# Sheet1.net
KiCad netlist of a schematic drawn in Altium Designer
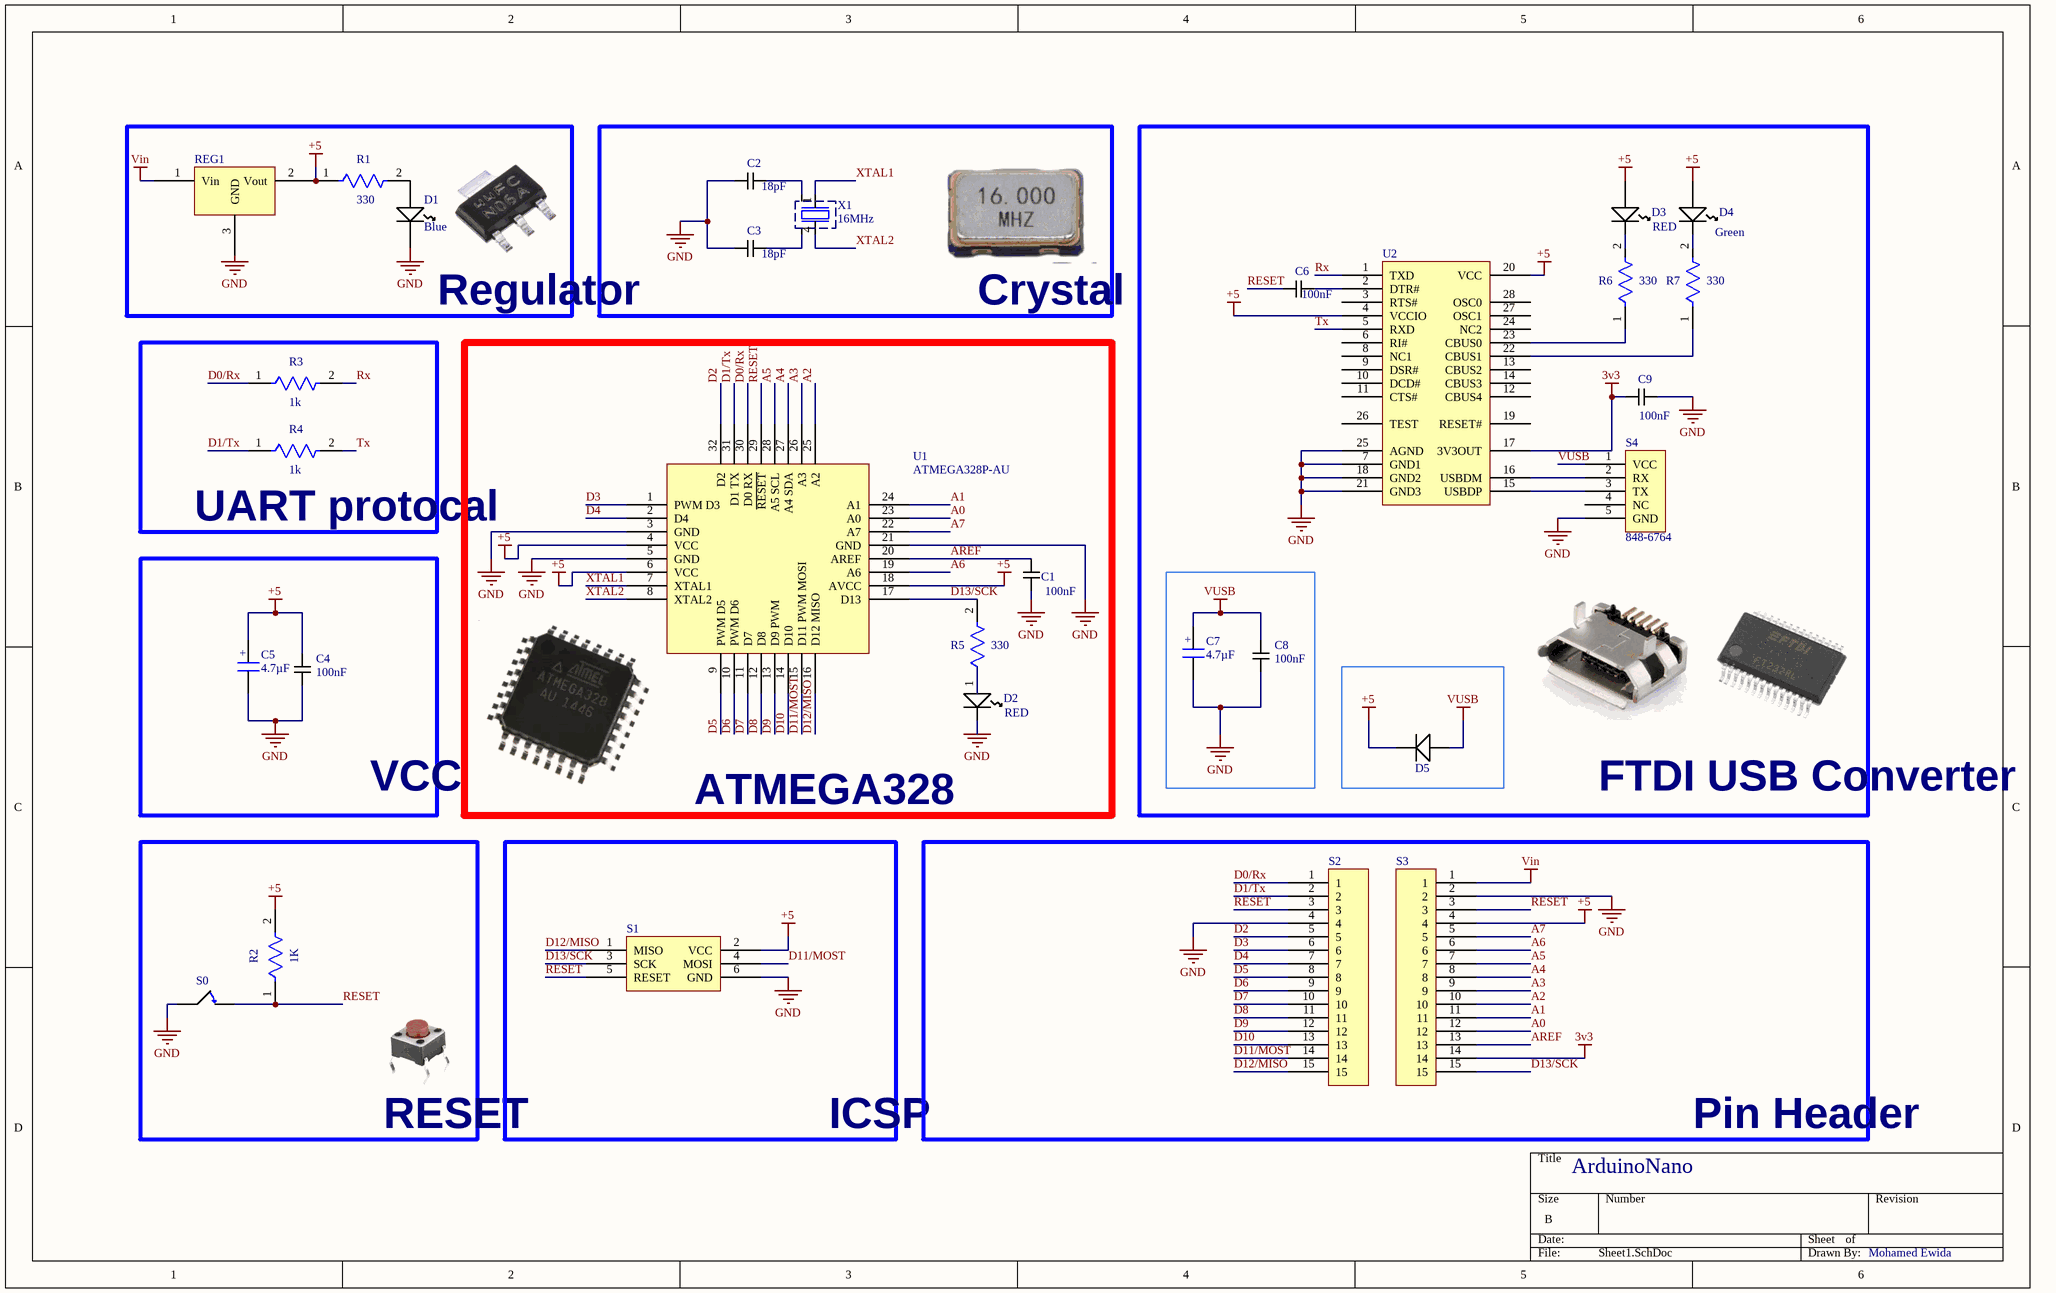
[diagram p0: Sheet1.SchDoc]

(export (version "E")
  (design (tool "Eeschema 10.0.6"))
  (components
    (comp (ref "C1")
      (value "100nF Ceramic Multilayer Capacitor_1")
      (footprint "CAPCP2012X09N")
      (description "AVX 0805 Standard 100nF Ceramic Multilayer Capacitor, 50 V dc X7R Dielectric ±10% SMD")
      (fields
        (field (name "MANUFACTURER") "AVX")
        (field (name "VOLTAGE") "50V")
        (field (name "CAPACITANCE") "100nF")
        (field (name "CREATOR") "Ritesh Kanjee")
      )
      (libsource (lib "RS Components - Capacitors") (part "100nF Ceramic Multilayer Capacitor_1"))
    )
    (comp (ref "C2")
      (value "C0805C180J5GACTU")
      (footprint "CAPCP2012X09N")
      (description "18pF Ceramic Multilayer Capacitor, 50 V dc C0G Dielectric ±5% SMD")
      (fields
        (field (name "MANUFACTURER") "Kemet")
        (field (name "VOLTAGE") "50V")
        (field (name "CAPACITANCE") "18pF")
        (field (name "CREATOR") "Ritesh Kanjee")
      )
      (libsource (lib "RS Components - Capacitors") (part "18pF Ceramic Multilayer Capacitor, 50 V dc C0G Dielectric ±5% SMD"))
    )
    (comp (ref "C3")
      (value "C0805C180J5GACTU")
      (footprint "CAPCP2012X09N")
      (description "18pF Ceramic Multilayer Capacitor, 50 V dc C0G Dielectric ±5% SMD")
      (fields
        (field (name "MANUFACTURER") "Kemet")
        (field (name "VOLTAGE") "50V")
        (field (name "CAPACITANCE") "18pF")
        (field (name "CREATOR") "Ritesh Kanjee")
      )
      (libsource (lib "RS Components - Capacitors") (part "18pF Ceramic Multilayer Capacitor, 50 V dc C0G Dielectric ±5% SMD"))
    )
    (comp (ref "C4")
      (value "100nF Ceramic Multilayer Capacitor_1")
      (footprint "CAPCP2012X09N")
      (description "AVX 0805 Standard 100nF Ceramic Multilayer Capacitor, 50 V dc X7R Dielectric ±10% SMD")
      (fields
        (field (name "MANUFACTURER") "AVX")
        (field (name "VOLTAGE") "50V")
        (field (name "CAPACITANCE") "100nF")
        (field (name "CREATOR") "Ritesh Kanjee")
      )
      (libsource (lib "RS Components - Capacitors") (part "100nF Ceramic Multilayer Capacitor_1"))
    )
    (comp (ref "C5")
      (value "4.7µF")
      (footprint "CASE A - 3216X18")
      (description "Capacitor,tantalum,SMT,16V,4.7uF,10%,A-case")
      (fields
        (field (name "TOLERANCE") "10%")
        (field (name "VOLTAGE") "16V")
        (field (name "PUBLISHER") "DPSS")
      )
      (libsource (lib "RS Components - Capacitors") (part "4.7µF Tant RS 496-3545"))
    )
    (comp (ref "C6")
      (value "100nF Ceramic Multilayer Capacitor_1")
      (footprint "CAPCP2012X09N")
      (description "AVX 0805 Standard 100nF Ceramic Multilayer Capacitor, 50 V dc X7R Dielectric ±10% SMD")
      (fields
        (field (name "MANUFACTURER") "AVX")
        (field (name "VOLTAGE") "50V")
        (field (name "CAPACITANCE") "100nF")
        (field (name "CREATOR") "Ritesh Kanjee")
      )
      (libsource (lib "RS Components - Capacitors") (part "100nF Ceramic Multilayer Capacitor_1"))
    )
    (comp (ref "C7")
      (value "4.7µF")
      (footprint "CASE A - 3216X18")
      (description "Capacitor,tantalum,SMT,16V,4.7uF,10%,A-case")
      (fields
        (field (name "TOLERANCE") "10%")
        (field (name "VOLTAGE") "16V")
        (field (name "PUBLISHER") "DPSS")
      )
      (libsource (lib "RS Components - Capacitors") (part "4.7µF Tant RS 496-3545"))
    )
    (comp (ref "C8")
      (value "100nF Ceramic Multilayer Capacitor_1")
      (footprint "CAPCP2012X09N")
      (description "AVX 0805 Standard 100nF Ceramic Multilayer Capacitor, 50 V dc X7R Dielectric ±10% SMD")
      (fields
        (field (name "MANUFACTURER") "AVX")
        (field (name "VOLTAGE") "50V")
        (field (name "CAPACITANCE") "100nF")
        (field (name "CREATOR") "Ritesh Kanjee")
      )
      (libsource (lib "RS Components - Capacitors") (part "100nF Ceramic Multilayer Capacitor_1"))
    )
    (comp (ref "C9")
      (value "100nF Ceramic Multilayer Capacitor_1")
      (footprint "CAPCP2012X09N")
      (description "AVX 0805 Standard 100nF Ceramic Multilayer Capacitor, 50 V dc X7R Dielectric ±10% SMD")
      (fields
        (field (name "MANUFACTURER") "AVX")
        (field (name "VOLTAGE") "50V")
        (field (name "CAPACITANCE") "100nF")
        (field (name "CREATOR") "Ritesh Kanjee")
      )
      (libsource (lib "RS Components - Capacitors") (part "100nF Ceramic Multilayer Capacitor_1"))
    )
    (comp (ref "D1")
      (value "Kingbright Blue LED, 60 mcd 120 ° 0805")
      (footprint "LED1913X12NBLUE")
      (fields
        (field (name "MANUFACTURER") "KingBright")
        (field (name "MANUFACTURER PART NO.") "KP-2012PBC-A")
        (field (name "CREATOR") "Ritesh Kanjee")
      )
      (libsource (lib "KingBright LEDs") (part "Kingbright Blue LED, 60 mcd 120 ° 0805"))
    )
    (comp (ref "D2")
      (value "Kingbright Red LED, 100 mcd 120 ° 0805")
      (footprint "LED1913X12NRED")
      (fields
        (field (name "MANUFACTURER") "KingBright")
        (field (name "MANUFACTURER PART NO.") "KP-2012SRC-PRV")
        (field (name "COLOR") "RED")
        (field (name "CREATOR") "Ritesh Kanjee")
      )
      (libsource (lib "KingBright LEDs") (part "Kingbright Red LED, 100 mcd 120 ° 0805"))
    )
    (comp (ref "D3")
      (value "Kingbright Red LED, 100 mcd 120 ° 0805")
      (footprint "LED1913X12NRED")
      (fields
        (field (name "MANUFACTURER") "KingBright")
        (field (name "MANUFACTURER PART NO.") "KP-2012SRC-PRV")
        (field (name "COLOR") "RED")
        (field (name "CREATOR") "Ritesh Kanjee")
      )
      (libsource (lib "KingBright LEDs") (part "Kingbright Red LED, 100 mcd 120 ° 0805"))
    )
    (comp (ref "D4")
      (value "Kingbright Green LED, 70 mcd 120 ° 0805")
      (footprint "LED1913X12NGREEN")
      (fields
        (field (name "MANUFACTURER") "KingBright")
        (field (name "MANUFACTURER PART NO.") "KP-2012MGC")
        (field (name "COLOR") "Green")
        (field (name "CREATOR") "Ritesh Kanjee")
      )
      (libsource (lib "KingBright LEDs") (part "Kingbright Green LED, 70 mcd 120 ° 0805"))
    )
    (comp (ref "D5")
      (value "Panasonic DB2J20900L Schottky Diode, 0.5A, 20V, 2.4ns, 2-Pin SMini2 F5 B")
      (footprint "DIOM1712X07N")
      (fields
        (field (name "MANUFACTURER") "Panasonic")
        (field (name "MANUFACTURER PART NO.") "DB2J20900L")
        (field (name "CREATED BY") "R Kanjee")
      )
      (libsource (lib "Panasonic Diodes") (part "Schottky Diode, 0.5A, 20V, 2.4ns, 2-Pin SMini2 F5 B"))
    )
    (comp (ref "R1")
      (value "ERA-3AEB102V")
      (footprint "FP-ERA3A-IPC_C")
      (description "RES SMD 1K OHM 0.1% 1/10W 0603")
      (fields (field (name "TOLERANCE") "0.1%"))
      (libsource (lib "Altium Content Vault") (part "1029c3af85768c4190bb7ad29bc67b5"))
    )
    (comp (ref "R2")
      (value "ERA-3AEB102V")
      (footprint "FP-ERA3A-IPC_C")
      (description "RES SMD 1K OHM 0.1% 1/10W 0603")
      (fields (field (name "TOLERANCE") "0.1%"))
      (libsource (lib "Altium Content Vault") (part "1029c3af85768c4190bb7ad29bc67b5"))
    )
    (comp (ref "R3")
      (value "ERA-3AEB102V")
      (footprint "FP-ERA3A-IPC_C")
      (description "RES SMD 1K OHM 0.1% 1/10W 0603")
      (fields (field (name "TOLERANCE") "0.1%") (field (name "RESISTANCE") "1k"))
      (libsource (lib "Altium Content Vault") (part "1029c3af85768c4190bb7ad29bc67b5"))
    )
    (comp (ref "R4")
      (value "ERA-3AEB102V")
      (footprint "FP-ERA3A-IPC_C")
      (description "RES SMD 1K OHM 0.1% 1/10W 0603")
      (fields (field (name "TOLERANCE") "0.1%") (field (name "RESISTANCE") "1k"))
      (libsource (lib "Altium Content Vault") (part "1029c3af85768c4190bb7ad29bc67b5"))
    )
    (comp (ref "R5")
      (value "ERA-3AEB102V")
      (footprint "FP-ERA3A-IPC_C")
      (description "RES SMD 1K OHM 0.1% 1/10W 0603")
      (fields (field (name "TOLERANCE") "0.1%") (field (name "RESISTANCE") "330"))
      (libsource (lib "Altium Content Vault") (part "1029c3af85768c4190bb7ad29bc67b5"))
    )
    (comp (ref "R6")
      (value "ERA-3AEB102V")
      (footprint "FP-ERA3A-IPC_C")
      (description "RES SMD 1K OHM 0.1% 1/10W 0603")
      (fields (field (name "TOLERANCE") "0.1%") (field (name "RESISTANCE") "330"))
      (libsource (lib "Altium Content Vault") (part "1029c3af85768c4190bb7ad29bc67b5"))
    )
    (comp (ref "R7")
      (value "ERA-3AEB102V")
      (footprint "FP-ERA3A-IPC_C")
      (description "RES SMD 1K OHM 0.1% 1/10W 0603")
      (fields (field (name "TOLERANCE") "0.1%") (field (name "RESISTANCE") "330"))
      (libsource (lib "Altium Content Vault") (part "1029c3af85768c4190bb7ad29bc67b5"))
    )
    (comp (ref "REG1")
      (value "LM1117MP-5.0/NOPB, Low Dropout Voltage Regulator, 1.5A, 5 V ±1%, 4-Pin SOT-223")
      (footprint "SOT230P700X180-4N")
      (fields (field (name "MANUFACTURER") "Texas Instruments") (field (name "CREATED BY") "R Kanjee"))
      (libsource (lib "TI Low Dropout Voltage Regulator") (part "LM1117MP-5.0"))
    )
    (comp (ref "S0")
      (value "Tactile Switch SPST- NO 0.05A @24V")
      (footprint "Tactile Switch")
      (fields
        (field (name "MANUFACTURER") "Omron")
        (field (name "MANUFACTURER PART NO.") "B3F1000")
        (field (name "CREATOR") "R Kanjee")
      )
      (libsource (lib "Omron Tactile Switches") (part "Tactile Switch SPST- NO 0.05A @24V"))
    )
    (comp (ref "S1")
      (value "Programming Headers Dual Row")
      (footprint "ISP HEADER")
      (fields
        (field (name "MANUFACTURER") "FCI")
        (field (name "MANUFACTURER PART NO.") "68000-236HLF")
        (field (name "CREATED BY") "R Kanjee")
      )
      (libsource (lib "PCB Headers") (part "Programming ISP, Programming Headers Dual Row"))
    )
    (comp (ref "S2")
      (value "connector;str header;single row;.1 cont centers;.095 tail;gold or gtx;36 contact")
      (footprint "Header")
      (fields
        (field (name "MANUFACTURER") "FCI")
        (field (name "MANUFACTURER PART NO.") "68000-236HLF")
        (field (name "CREATED BY") "R Kanjee")
      )
      (libsource (lib "PCB Headers") (part "Single row; PCB headers"))
    )
    (comp (ref "S3")
      (value "connector;str header;single row;.1 cont centers;.095 tail;gold or gtx;36 contact")
      (footprint "Header")
      (fields
        (field (name "MANUFACTURER") "FCI")
        (field (name "MANUFACTURER PART NO.") "68000-236HLF")
        (field (name "CREATED BY") "R Kanjee")
      )
      (libsource (lib "") (part "Single row; PCB headers_1"))
    )
    (comp (ref "S4")
      (value "NewMolex Right Angle SMT Female Type B Micro USB Connector, 30 V ac, 1.8A")
      (footprint "MicroUSB")
      (fields
        (field (name "MANUFACTURER") "Molex")
        (field (name "MANUFACTURER PART NO.") "105017-0001")
        (field (name "RS STOCK NO") "848-6764")
        (field (name "CREATOR") "R Kanjee")
      )
      (libsource (lib "Molex Connectors") (part "Micro USB Connector, 30 V ac, 1.8A"))
    )
    (comp (ref "U1")
      (value "ATMEGA328P-AU")
      (footprint "TQFP80P900X900X120-32N")
      (description "ATMEGA328P-AU, 8 bit AVR Microcontroller 20MHz 1 kB, 32 kB Flash, 2 kB RAM, I2C 32-Pin TQFP")
      (fields (field (name "CREATED BY") "Ritesh Kanjee"))
      (libsource (lib "Atmel Microcontrollers") (part "ATMEGA328P-AU"))
    )
    (comp (ref "U2")
      (value "FT232RL, Universal Asynchronous Receiver & Transmitter 3MBd, 28-Pin, SSOP")
      (footprint "SOP65P780X200-28N")
      (fields
        (field (name "MANUFACTURER PART NO.") "FT232RL")
        (field (name "MANUFACTURER") "FTDI Chip")
        (field (name "CREATOR") "R Kanjee")
      )
      (libsource (lib "FTDI RS232toUSB") (part "FT232RL USB to UART, Universal Asynchronous Receiver & Transmitter 3MBd, 28-Pin, SSOP"))
    )
    (comp (ref "X1")
      (value "16MHz")
      (footprint "Aker S5C Crystal")
      (description "Aker S5C SMT Crystal")
      (fields
        (field (name "MANUFACTURER") "Aker")
        (field (name "MANUFACTURER PART #") "C5S-16.000-12-3030-X")
        (field (name "CREATOR") "R Kanjee")
      )
      (libsource (lib "Aker Crystals") (part "Aker  C5S-16.000-12-3030-X"))
    )
  )
  (nets
    (net (code "1") (name "+5") (class "Default")
      (node (ref "C4") (pin "2") (pinfunction "2_2") (pintype "passive"))
      (node (ref "C5") (pin "1") (pinfunction "1_1") (pintype "passive"))
      (node (ref "D3") (pin "1") (pinfunction "A_1") (pintype "passive"))
      (node (ref "D4") (pin "1") (pinfunction "A_1") (pintype "passive"))
      (node (ref "D5") (pin "1") (pinfunction "1_1") (pintype "passive"))
      (node (ref "R1") (pin "1") (pinfunction "1_1") (pintype "passive"))
      (node (ref "R2") (pin "2") (pinfunction "2_2") (pintype "passive"))
      (node (ref "REG1") (pin "2") (pinfunction "Vout_2") (pintype "passive"))
      (node (ref "S1") (pin "2") (pinfunction "VCC_2") (pintype "passive"))
      (node (ref "S3") (pin "4") (pinfunction "4_4") (pintype "passive"))
      (node (ref "U1") (pin "18") (pinfunction "AVCC_18") (pintype "passive"))
      (node (ref "U1") (pin "4") (pinfunction "VCC_4") (pintype "passive"))
      (node (ref "U1") (pin "6") (pinfunction "VCC_6") (pintype "passive"))
      (node (ref "U2") (pin "20") (pinfunction "VCC_20") (pintype "passive"))
      (node (ref "U2") (pin "4") (pinfunction "VCCIO_4") (pintype "passive"))
    )
    (net (code "2") (name "/A0") (class "Default")
      (node (ref "S3") (pin "12") (pinfunction "12_12") (pintype "passive"))
      (node (ref "U1") (pin "23") (pinfunction "A0_23") (pintype "passive"))
    )
    (net (code "3") (name "/A1") (class "Default")
      (node (ref "S3") (pin "11") (pinfunction "11_11") (pintype "passive"))
      (node (ref "U1") (pin "24") (pinfunction "A1_24") (pintype "passive"))
    )
    (net (code "4") (name "/A2") (class "Default")
      (node (ref "S3") (pin "10") (pinfunction "10_10") (pintype "passive"))
      (node (ref "U1") (pin "25") (pinfunction "A2_25") (pintype "passive"))
    )
    (net (code "5") (name "/A3") (class "Default")
      (node (ref "S3") (pin "9") (pinfunction "9_9") (pintype "passive"))
      (node (ref "U1") (pin "26") (pinfunction "A3_26") (pintype "passive"))
    )
    (net (code "6") (name "/A4") (class "Default")
      (node (ref "S3") (pin "8") (pinfunction "8_8") (pintype "passive"))
      (node (ref "U1") (pin "27") (pinfunction "A4_SDA_27") (pintype "passive"))
    )
    (net (code "7") (name "/A5") (class "Default")
      (node (ref "S3") (pin "7") (pinfunction "7_7") (pintype "passive"))
      (node (ref "U1") (pin "28") (pinfunction "A5_SCL_28") (pintype "passive"))
    )
    (net (code "8") (name "/A6") (class "Default")
      (node (ref "S3") (pin "6") (pinfunction "6_6") (pintype "passive"))
      (node (ref "U1") (pin "19") (pinfunction "A6_19") (pintype "passive"))
    )
    (net (code "9") (name "/A7") (class "Default")
      (node (ref "S3") (pin "5") (pinfunction "5_5") (pintype "passive"))
      (node (ref "U1") (pin "22") (pinfunction "A7_22") (pintype "passive"))
    )
    (net (code "10") (name "/AREF") (class "Default")
      (node (ref "C1") (pin "2") (pinfunction "2_2") (pintype "passive"))
      (node (ref "S3") (pin "13") (pinfunction "13_13") (pintype "passive"))
      (node (ref "U1") (pin "20") (pinfunction "AREF_20") (pintype "passive"))
    )
    (net (code "11") (name "/D0{slash}Rx") (class "Default")
      (node (ref "R3") (pin "1") (pinfunction "1_1") (pintype "passive"))
      (node (ref "S2") (pin "1") (pinfunction "1_1") (pintype "passive"))
      (node (ref "U1") (pin "30") (pinfunction "D0_RX_30") (pintype "passive"))
    )
    (net (code "12") (name "/D1{slash}Tx") (class "Default")
      (node (ref "R4") (pin "1") (pinfunction "1_1") (pintype "passive"))
      (node (ref "S2") (pin "2") (pinfunction "2_2") (pintype "passive"))
      (node (ref "U1") (pin "31") (pinfunction "D1_TX_31") (pintype "passive"))
    )
    (net (code "13") (name "/D2") (class "Default")
      (node (ref "S2") (pin "5") (pinfunction "5_5") (pintype "passive"))
      (node (ref "U1") (pin "32") (pinfunction "D2_32") (pintype "passive"))
    )
    (net (code "14") (name "/D3") (class "Default")
      (node (ref "S2") (pin "6") (pinfunction "6_6") (pintype "passive"))
      (node (ref "U1") (pin "1") (pinfunction "PWM_D3_1") (pintype "passive"))
    )
    (net (code "15") (name "/D4") (class "Default")
      (node (ref "S2") (pin "7") (pinfunction "7_7") (pintype "passive"))
      (node (ref "U1") (pin "2") (pinfunction "D4_2") (pintype "passive"))
    )
    (net (code "16") (name "/D5") (class "Default")
      (node (ref "S2") (pin "8") (pinfunction "8_8") (pintype "passive"))
      (node (ref "U1") (pin "9") (pinfunction "PWM_D5_9") (pintype "passive"))
    )
    (net (code "17") (name "/D6") (class "Default")
      (node (ref "S2") (pin "9") (pinfunction "9_9") (pintype "passive"))
      (node (ref "U1") (pin "10") (pinfunction "PWM_D6_10") (pintype "passive"))
    )
    (net (code "18") (name "/D7") (class "Default")
      (node (ref "S2") (pin "10") (pinfunction "10_10") (pintype "passive"))
      (node (ref "U1") (pin "11") (pinfunction "D7_11") (pintype "passive"))
    )
    (net (code "19") (name "/D8") (class "Default")
      (node (ref "S2") (pin "11") (pinfunction "11_11") (pintype "passive"))
      (node (ref "U1") (pin "12") (pinfunction "D8_12") (pintype "passive"))
    )
    (net (code "20") (name "/D9") (class "Default")
      (node (ref "S2") (pin "12") (pinfunction "12_12") (pintype "passive"))
      (node (ref "U1") (pin "13") (pinfunction "D9_PWM_13") (pintype "passive"))
    )
    (net (code "21") (name "/D10") (class "Default")
      (node (ref "S2") (pin "13") (pinfunction "13_13") (pintype "passive"))
      (node (ref "U1") (pin "14") (pinfunction "D10_14") (pintype "passive"))
    )
    (net (code "22") (name "/D11{slash}MOST") (class "Default")
      (node (ref "S1") (pin "4") (pinfunction "MOSI_4") (pintype "passive"))
      (node (ref "S2") (pin "14") (pinfunction "14_14") (pintype "passive"))
      (node (ref "U1") (pin "15") (pinfunction "D11_PWM_MOSI_15") (pintype "passive"))
    )
    (net (code "23") (name "/D12{slash}MISO") (class "Default")
      (node (ref "S1") (pin "1") (pinfunction "MISO_1") (pintype "passive"))
      (node (ref "S2") (pin "15") (pinfunction "15_15") (pintype "passive"))
      (node (ref "U1") (pin "16") (pinfunction "D12_MISO_16") (pintype "passive"))
    )
    (net (code "24") (name "/D13{slash}SCK") (class "Default")
      (node (ref "R5") (pin "2") (pinfunction "2_2") (pintype "passive"))
      (node (ref "S1") (pin "3") (pinfunction "SCK_3") (pintype "passive"))
      (node (ref "S3") (pin "15") (pinfunction "15_15") (pintype "passive"))
      (node (ref "U1") (pin "17") (pinfunction "D13_17") (pintype "passive"))
    )
    (net (code "25") (name "/RESET") (class "Default")
      (node (ref "C6") (pin "1") (pinfunction "1_1") (pintype "passive"))
      (node (ref "R2") (pin "1") (pinfunction "1_1") (pintype "passive"))
      (node (ref "S0") (pin "1") (pinfunction "1_1") (pintype "passive"))
      (node (ref "S1") (pin "5") (pinfunction "RESET_5") (pintype "passive"))
      (node (ref "S2") (pin "3") (pinfunction "3_3") (pintype "passive"))
      (node (ref "S3") (pin "3") (pinfunction "3_3") (pintype "passive"))
      (node (ref "U1") (pin "29") (pinfunction "~{RESET}_29") (pintype "passive"))
    )
    (net (code "26") (name "/Rx") (class "Default")
      (node (ref "R3") (pin "2") (pinfunction "2_2") (pintype "passive"))
      (node (ref "U2") (pin "1") (pinfunction "TXD_1") (pintype "passive"))
    )
    (net (code "27") (name "/Tx") (class "Default")
      (node (ref "R4") (pin "2") (pinfunction "2_2") (pintype "passive"))
      (node (ref "U2") (pin "5") (pinfunction "RXD_5") (pintype "passive"))
    )
    (net (code "28") (name "/XTAL1") (class "Default")
      (node (ref "U1") (pin "7") (pinfunction "XTAL1_7") (pintype "passive"))
      (node (ref "X1") (pin "1") (pinfunction "1_1") (pintype "passive"))
    )
    (net (code "29") (name "/XTAL2") (class "Default")
      (node (ref "U1") (pin "8") (pinfunction "XTAL2_8") (pintype "passive"))
      (node (ref "X1") (pin "4") (pinfunction "4_4") (pintype "passive"))
    )
    (net (code "30") (name "3v3") (class "Default")
      (node (ref "C9") (pin "1") (pinfunction "1_1") (pintype "passive"))
      (node (ref "S3") (pin "14") (pinfunction "14_14") (pintype "passive"))
      (node (ref "U2") (pin "17") (pinfunction "3V3OUT_17") (pintype "passive"))
    )
    (net (code "31") (name "GND") (class "Default")
      (node (ref "C1") (pin "1") (pinfunction "1_1") (pintype "passive"))
      (node (ref "C2") (pin "1") (pinfunction "1_1") (pintype "passive"))
      (node (ref "C3") (pin "1") (pinfunction "1_1") (pintype "passive"))
      (node (ref "C4") (pin "1") (pinfunction "1_1") (pintype "passive"))
      (node (ref "C5") (pin "2") (pinfunction "2_2") (pintype "passive"))
      (node (ref "C7") (pin "2") (pinfunction "2_2") (pintype "passive"))
      (node (ref "C8") (pin "1") (pinfunction "1_1") (pintype "passive"))
      (node (ref "C9") (pin "2") (pinfunction "2_2") (pintype "passive"))
      (node (ref "D1") (pin "2") (pinfunction "K_2") (pintype "passive"))
      (node (ref "D2") (pin "2") (pinfunction "K_2") (pintype "passive"))
      (node (ref "S0") (pin "1") (pinfunction "1_1") (pintype "passive"))
      (node (ref "S1") (pin "6") (pinfunction "GND_6") (pintype "passive"))
      (node (ref "S2") (pin "4") (pinfunction "4_4") (pintype "passive"))
      (node (ref "S3") (pin "2") (pinfunction "2_2") (pintype "passive"))
      (node (ref "S4") (pin "5") (pinfunction "GND_5") (pintype "passive"))
      (node (ref "U1") (pin "21") (pinfunction "GND_21") (pintype "passive"))
      (node (ref "U1") (pin "3") (pinfunction "GND_3") (pintype "passive"))
      (node (ref "U1") (pin "5") (pinfunction "GND_5") (pintype "passive"))
      (node (ref "U2") (pin "18") (pinfunction "GND2_18") (pintype "passive"))
      (node (ref "U2") (pin "21") (pinfunction "GND3_21") (pintype "passive"))
      (node (ref "U2") (pin "25") (pinfunction "AGND_25") (pintype "passive"))
      (node (ref "U2") (pin "7") (pinfunction "GND1_7") (pintype "passive"))
    )
    (net (code "32") (name "Net-(C2-Pad2)") (class "Default")
      (node (ref "C2") (pin "2") (pinfunction "2_2") (pintype "passive"))
      (node (ref "X1") (pin "3") (pinfunction "Gnd_3") (pintype "power_in"))
    )
    (net (code "33") (name "Net-(C3-Pad2)") (class "Default")
      (node (ref "C3") (pin "2") (pinfunction "2_2") (pintype "passive"))
      (node (ref "X1") (pin "2") (pinfunction "Gnd_2") (pintype "power_in"))
    )
    (net (code "34") (name "Net-(D1-A)") (class "Default")
      (node (ref "D1") (pin "1") (pinfunction "A_1") (pintype "passive"))
      (node (ref "R1") (pin "2") (pinfunction "2_2") (pintype "passive"))
    )
    (net (code "35") (name "Net-(D2-A)") (class "Default")
      (node (ref "D2") (pin "1") (pinfunction "A_1") (pintype "passive"))
      (node (ref "R5") (pin "1") (pinfunction "1_1") (pintype "passive"))
    )
    (net (code "36") (name "Net-(D3-K)") (class "Default")
      (node (ref "D3") (pin "2") (pinfunction "K_2") (pintype "passive"))
      (node (ref "R6") (pin "2") (pinfunction "2_2") (pintype "passive"))
    )
    (net (code "37") (name "Net-(D4-K)") (class "Default")
      (node (ref "D4") (pin "2") (pinfunction "K_2") (pintype "passive"))
      (node (ref "R7") (pin "2") (pinfunction "2_2") (pintype "passive"))
    )
    (net (code "38") (name "Net-(S4-RX)") (class "Default")
      (node (ref "S4") (pin "2") (pinfunction "RX_2") (pintype "passive"))
      (node (ref "U2") (pin "16") (pinfunction "USBDM_16") (pintype "passive"))
    )
    (net (code "39") (name "Net-(S4-TX)") (class "Default")
      (node (ref "S4") (pin "3") (pinfunction "TX_3") (pintype "passive"))
      (node (ref "U2") (pin "15") (pinfunction "USBDP_15") (pintype "passive"))
    )
    (net (code "40") (name "Net-(U2-CBUS0)") (class "Default")
      (node (ref "R6") (pin "1") (pinfunction "1_1") (pintype "passive"))
      (node (ref "U2") (pin "23") (pinfunction "CBUS0_23") (pintype "passive"))
    )
    (net (code "41") (name "Net-(U2-CBUS1)") (class "Default")
      (node (ref "R7") (pin "1") (pinfunction "1_1") (pintype "passive"))
      (node (ref "U2") (pin "22") (pinfunction "CBUS1_22") (pintype "passive"))
    )
    (net (code "42") (name "Net-(U2-DTR#)") (class "Default")
      (node (ref "C6") (pin "2") (pinfunction "2_2") (pintype "passive"))
      (node (ref "U2") (pin "2") (pinfunction "DTR#_2") (pintype "passive"))
    )
    (net (code "43") (name "VUSB") (class "Default")
      (node (ref "C7") (pin "1") (pinfunction "1_1") (pintype "passive"))
      (node (ref "C8") (pin "2") (pinfunction "2_2") (pintype "passive"))
      (node (ref "D5") (pin "2") (pinfunction "2_2") (pintype "passive"))
      (node (ref "S4") (pin "1") (pinfunction "VCC_1") (pintype "passive"))
    )
    (net (code "44") (name "Vin") (class "Default")
      (node (ref "REG1") (pin "1") (pinfunction "Vin_1") (pintype "passive"))
      (node (ref "S3") (pin "1") (pinfunction "1_1") (pintype "passive"))
    )
    (net (code "45") (name "unconnected-(REG1-GND-Pad3)") (class "Default")
      (node (ref "REG1") (pin "3") (pinfunction "GND_3") (pintype "passive"))
    )
    (net (code "46") (name "unconnected-(S4-NC-Pad4)") (class "Default")
      (node (ref "S4") (pin "4") (pinfunction "NC_4") (pintype "passive"))
    )
    (net (code "47") (name "unconnected-(U2-CBUS2-Pad13)") (class "Default")
      (node (ref "U2") (pin "13") (pinfunction "CBUS2_13") (pintype "passive"))
    )
    (net (code "48") (name "unconnected-(U2-CBUS3-Pad14)") (class "Default")
      (node (ref "U2") (pin "14") (pinfunction "CBUS3_14") (pintype "passive"))
    )
    (net (code "49") (name "unconnected-(U2-CBUS4-Pad12)") (class "Default")
      (node (ref "U2") (pin "12") (pinfunction "CBUS4_12") (pintype "passive"))
    )
    (net (code "50") (name "unconnected-(U2-CTS#-Pad11)") (class "Default")
      (node (ref "U2") (pin "11") (pinfunction "CTS#_11") (pintype "passive"))
    )
    (net (code "51") (name "unconnected-(U2-DCD#-Pad10)") (class "Default")
      (node (ref "U2") (pin "10") (pinfunction "DCD#_10") (pintype "passive"))
    )
    (net (code "52") (name "unconnected-(U2-DSR#-Pad9)") (class "Default")
      (node (ref "U2") (pin "9") (pinfunction "DSR#_9") (pintype "passive"))
    )
    (net (code "53") (name "unconnected-(U2-NC1-Pad8)") (class "Default")
      (node (ref "U2") (pin "8") (pinfunction "NC1_8") (pintype "passive"))
    )
    (net (code "54") (name "unconnected-(U2-NC2-Pad24)") (class "Default")
      (node (ref "U2") (pin "24") (pinfunction "NC2_24") (pintype "passive"))
    )
    (net (code "55") (name "unconnected-(U2-OSC0-Pad28)") (class "Default")
      (node (ref "U2") (pin "28") (pinfunction "OSC0_28") (pintype "passive"))
    )
    (net (code "56") (name "unconnected-(U2-OSC1-Pad27)") (class "Default")
      (node (ref "U2") (pin "27") (pinfunction "OSC1_27") (pintype "passive"))
    )
    (net (code "57") (name "unconnected-(U2-RESET#-Pad19)") (class "Default")
      (node (ref "U2") (pin "19") (pinfunction "RESET#_19") (pintype "passive"))
    )
    (net (code "58") (name "unconnected-(U2-RI#-Pad6)") (class "Default")
      (node (ref "U2") (pin "6") (pinfunction "RI#_6") (pintype "passive"))
    )
    (net (code "59") (name "unconnected-(U2-RTS#-Pad3)") (class "Default")
      (node (ref "U2") (pin "3") (pinfunction "RTS#_3") (pintype "passive"))
    )
    (net (code "60") (name "unconnected-(U2-TEST-Pad26)") (class "Default")
      (node (ref "U2") (pin "26") (pinfunction "TEST_26") (pintype "passive"))
    )
  )
)
